# Interface.net
KiCad netlist of a schematic drawn in Altium Designer
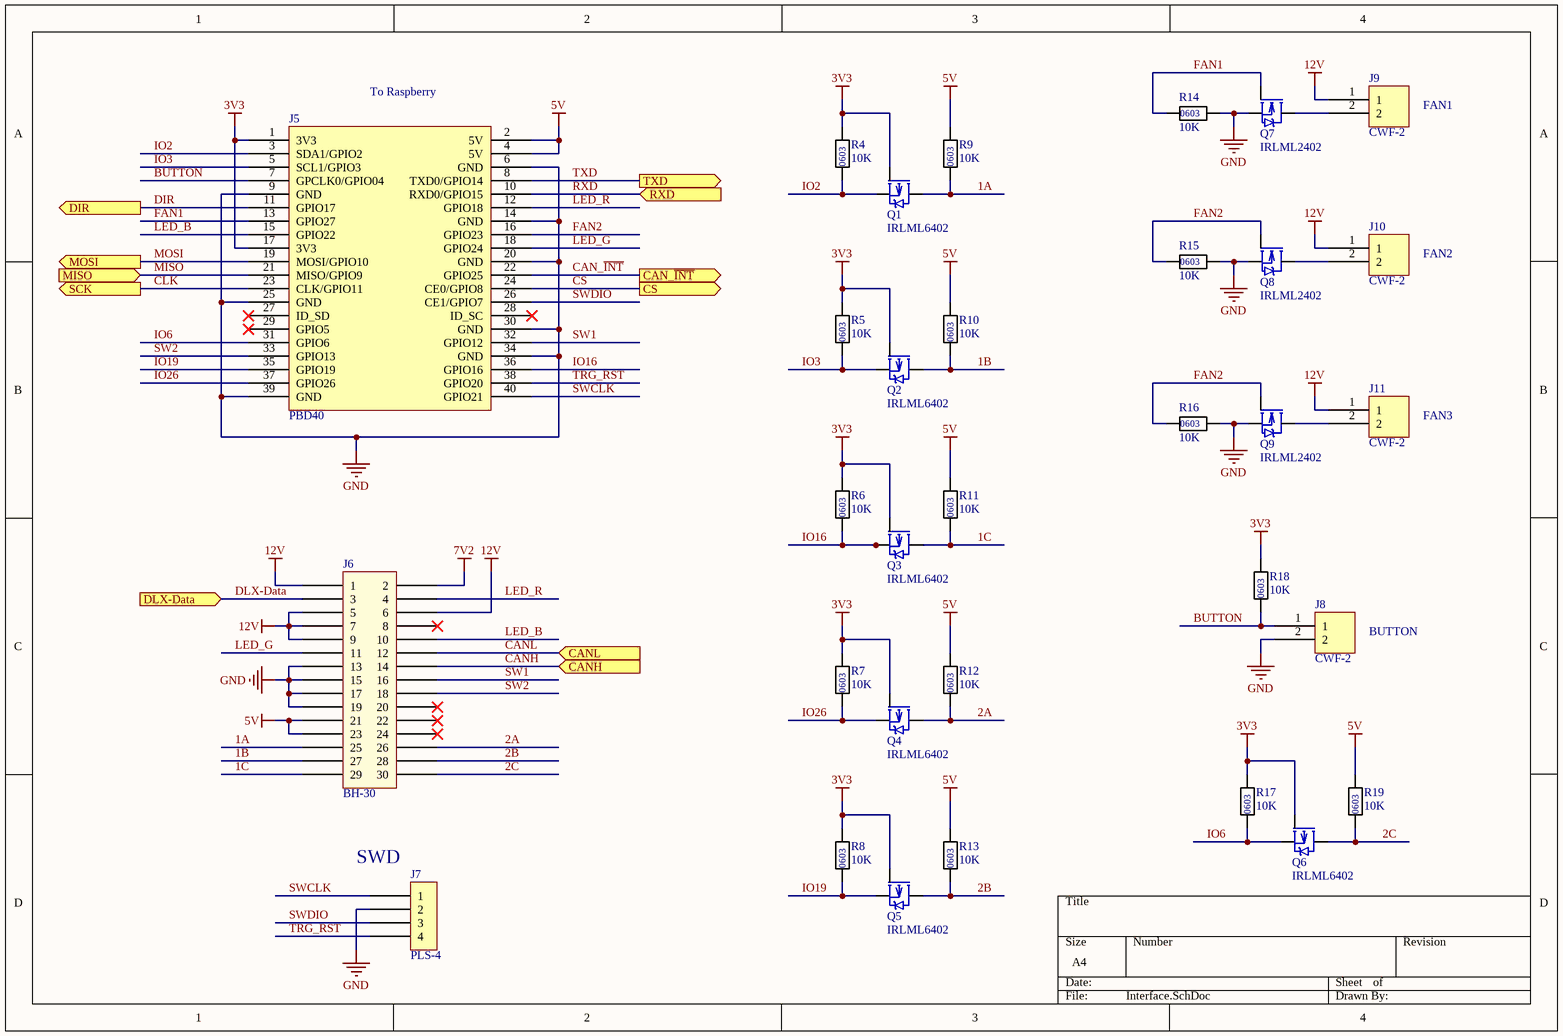
[diagram p0: Interface.SchDoc]

(export (version "E")
  (design (tool "Eeschema 10.0.6"))
  (components
    (comp (ref "J5") (value "PBD40") (footprint "PLD40") (libsource (lib "Popular") (part "RPiGPIO")))
    (comp (ref "J6") (value "BH-30") (footprint "BH-30") (libsource (lib "Popular") (part "BH-30")))
    (comp (ref "J7") (value "PLS-4") (footprint "PLS-4") (libsource (lib "Popular") (part "PLS-4")))
    (comp (ref "J8")
      (value "CWF-2")
      (footprint "CWF-2")
      (description "Connector")
      (libsource (lib "Popular") (part "CWF-2"))
    )
    (comp (ref "J9")
      (value "CWF-2")
      (footprint "CWF-2")
      (description "Connector")
      (libsource (lib "Popular") (part "CWF-2"))
    )
    (comp (ref "J10")
      (value "CWF-2")
      (footprint "CWF-2")
      (description "Connector")
      (libsource (lib "Popular") (part "CWF-2"))
    )
    (comp (ref "J11")
      (value "CWF-2")
      (footprint "CWF-2")
      (description "Connector")
      (libsource (lib "Popular") (part "CWF-2"))
    )
    (comp (ref "Q1")
      (value "IRLML6402")
      (footprint "SOT23")
      (description "p-chanal MOSFET")
      (libsource (lib "Popular") (part "IRLML6402"))
    )
    (comp (ref "Q2")
      (value "IRLML6402")
      (footprint "SOT23")
      (description "p-chanal MOSFET")
      (libsource (lib "Popular") (part "IRLML6402"))
    )
    (comp (ref "Q3")
      (value "IRLML6402")
      (footprint "SOT23")
      (description "p-chanal MOSFET")
      (libsource (lib "Popular") (part "IRLML6402"))
    )
    (comp (ref "Q4")
      (value "IRLML6402")
      (footprint "SOT23")
      (description "p-chanal MOSFET")
      (libsource (lib "Popular") (part "IRLML6402"))
    )
    (comp (ref "Q5")
      (value "IRLML6402")
      (footprint "SOT23")
      (description "p-chanal MOSFET")
      (libsource (lib "Popular") (part "IRLML6402"))
    )
    (comp (ref "Q6")
      (value "IRLML6402")
      (footprint "SOT23")
      (description "p-chanal MOSFET")
      (libsource (lib "Popular") (part "IRLML6402"))
    )
    (comp (ref "Q7")
      (value "IRLML2402")
      (footprint "SOT23")
      (description "n-chanal MOSFET")
      (libsource (lib "Popular") (part "IRLML2402"))
    )
    (comp (ref "Q8")
      (value "IRLML2402")
      (footprint "SOT23")
      (description "n-chanal MOSFET")
      (libsource (lib "Popular") (part "IRLML2402"))
    )
    (comp (ref "Q9")
      (value "IRLML2402")
      (footprint "SOT23")
      (description "n-chanal MOSFET")
      (libsource (lib "Popular") (part "IRLML2402"))
    )
    (comp (ref "R4") (value "10K") (footprint "CHIP_R_0603") (libsource (lib "Popular") (part "RES_0603")))
    (comp (ref "R5") (value "10K") (footprint "CHIP_R_0603") (libsource (lib "Popular") (part "RES_0603")))
    (comp (ref "R6") (value "10K") (footprint "CHIP_R_0603") (libsource (lib "Popular") (part "RES_0603")))
    (comp (ref "R7") (value "10K") (footprint "CHIP_R_0603") (libsource (lib "Popular") (part "RES_0603")))
    (comp (ref "R8") (value "10K") (footprint "CHIP_R_0603") (libsource (lib "Popular") (part "RES_0603")))
    (comp (ref "R9") (value "10K") (footprint "CHIP_R_0603") (libsource (lib "Popular") (part "RES_0603")))
    (comp (ref "R10") (value "10K") (footprint "CHIP_R_0603") (libsource (lib "Popular") (part "RES_0603")))
    (comp (ref "R11") (value "10K") (footprint "CHIP_R_0603") (libsource (lib "Popular") (part "RES_0603")))
    (comp (ref "R12") (value "10K") (footprint "CHIP_R_0603") (libsource (lib "Popular") (part "RES_0603")))
    (comp (ref "R13") (value "10K") (footprint "CHIP_R_0603") (libsource (lib "Popular") (part "RES_0603")))
    (comp (ref "R14") (value "10K") (footprint "CHIP_R_0603") (libsource (lib "Popular") (part "RES_0603")))
    (comp (ref "R15") (value "10K") (footprint "CHIP_R_0603") (libsource (lib "Popular") (part "RES_0603")))
    (comp (ref "R16") (value "10K") (footprint "CHIP_R_0603") (libsource (lib "Popular") (part "RES_0603")))
    (comp (ref "R17") (value "10K") (footprint "CHIP_R_0603") (libsource (lib "Popular") (part "RES_0603")))
    (comp (ref "R18") (value "10K") (footprint "CHIP_R_0603") (libsource (lib "Popular") (part "RES_0603")))
    (comp (ref "R19") (value "10K") (footprint "CHIP_R_0603") (libsource (lib "Popular") (part "RES_0603")))
  )
  (nets
    (net (code "1") (name "/1A") (class "Default")
      (node (ref "J6") (pin "25") (pinfunction "25_25") (pintype "passive"))
      (node (ref "Q1") (pin "3") (pinfunction "D_3") (pintype "passive"))
      (node (ref "R9") (pin "1") (pinfunction "1_1") (pintype "passive"))
    )
    (net (code "2") (name "/1B") (class "Default")
      (node (ref "J6") (pin "27") (pinfunction "27_27") (pintype "passive"))
      (node (ref "Q2") (pin "3") (pinfunction "D_3") (pintype "passive"))
      (node (ref "R10") (pin "1") (pinfunction "1_1") (pintype "passive"))
    )
    (net (code "3") (name "/1C") (class "Default")
      (node (ref "J6") (pin "29") (pinfunction "29_29") (pintype "passive"))
      (node (ref "Q3") (pin "3") (pinfunction "D_3") (pintype "passive"))
      (node (ref "R11") (pin "1") (pinfunction "1_1") (pintype "passive"))
    )
    (net (code "4") (name "/2A") (class "Default")
      (node (ref "J6") (pin "26") (pinfunction "26_26") (pintype "passive"))
      (node (ref "Q4") (pin "3") (pinfunction "D_3") (pintype "passive"))
      (node (ref "R12") (pin "1") (pinfunction "1_1") (pintype "passive"))
    )
    (net (code "5") (name "/2B") (class "Default")
      (node (ref "J6") (pin "28") (pinfunction "28_28") (pintype "passive"))
      (node (ref "Q5") (pin "3") (pinfunction "D_3") (pintype "passive"))
      (node (ref "R13") (pin "1") (pinfunction "1_1") (pintype "passive"))
    )
    (net (code "6") (name "/2C") (class "Default")
      (node (ref "J6") (pin "30") (pinfunction "30_30") (pintype "passive"))
      (node (ref "Q6") (pin "3") (pinfunction "D_3") (pintype "passive"))
      (node (ref "R19") (pin "1") (pinfunction "1_1") (pintype "passive"))
    )
    (net (code "7") (name "/BUTTON") (class "Default")
      (node (ref "J5") (pin "7") (pinfunction "GPCLK0/GPIO04_7") (pintype "passive"))
      (node (ref "J8") (pin "1") (pinfunction "1_1") (pintype "passive"))
      (node (ref "R18") (pin "1") (pinfunction "1_1") (pintype "passive"))
    )
    (net (code "8") (name "/CANH") (class "Default")
      (node (ref "J6") (pin "14") (pinfunction "14_14") (pintype "passive"))
    )
    (net (code "9") (name "/CANL") (class "Default")
      (node (ref "J6") (pin "12") (pinfunction "12_12") (pintype "passive"))
    )
    (net (code "10") (name "/CAN_~{INT}") (class "Default")
      (node (ref "J5") (pin "22") (pinfunction "GPIO25_22") (pintype "passive"))
    )
    (net (code "11") (name "/CLK") (class "Default")
      (node (ref "J5") (pin "23") (pinfunction "CLK/GPIO11_23") (pintype "passive"))
    )
    (net (code "12") (name "/CS") (class "Default")
      (node (ref "J5") (pin "24") (pinfunction "CE0/GPIO8_24") (pintype "passive"))
    )
    (net (code "13") (name "/DIR") (class "Default")
      (node (ref "J5") (pin "11") (pinfunction "GPIO17_11") (pintype "passive"))
    )
    (net (code "14") (name "/DLX-Data") (class "Default")
      (node (ref "J6") (pin "3") (pinfunction "3_3") (pintype "passive"))
    )
    (net (code "15") (name "/FAN1") (class "Default")
      (node (ref "J5") (pin "13") (pinfunction "GPIO27_13") (pintype "passive"))
      (node (ref "Q7") (pin "1") (pinfunction "G_1") (pintype "passive"))
      (node (ref "R14") (pin "1") (pinfunction "1_1") (pintype "passive"))
    )
    (net (code "16") (name "/FAN2") (class "Default")
      (node (ref "J5") (pin "16") (pinfunction "GPIO23_16") (pintype "passive"))
      (node (ref "Q8") (pin "1") (pinfunction "G_1") (pintype "passive"))
      (node (ref "Q9") (pin "1") (pinfunction "G_1") (pintype "passive"))
      (node (ref "R15") (pin "1") (pinfunction "1_1") (pintype "passive"))
      (node (ref "R16") (pin "1") (pinfunction "1_1") (pintype "passive"))
    )
    (net (code "17") (name "/IO2") (class "Default")
      (node (ref "J5") (pin "3") (pinfunction "SDA1/GPIO2_3") (pintype "passive"))
      (node (ref "Q1") (pin "2") (pinfunction "S_2") (pintype "passive"))
      (node (ref "R4") (pin "1") (pinfunction "1_1") (pintype "passive"))
    )
    (net (code "18") (name "/IO3") (class "Default")
      (node (ref "J5") (pin "5") (pinfunction "SCL1/GPIO3_5") (pintype "passive"))
      (node (ref "Q2") (pin "2") (pinfunction "S_2") (pintype "passive"))
      (node (ref "R5") (pin "1") (pinfunction "1_1") (pintype "passive"))
    )
    (net (code "19") (name "/IO6") (class "Default")
      (node (ref "J5") (pin "31") (pinfunction "GPIO6_31") (pintype "passive"))
      (node (ref "Q6") (pin "2") (pinfunction "S_2") (pintype "passive"))
      (node (ref "R17") (pin "1") (pinfunction "1_1") (pintype "passive"))
    )
    (net (code "20") (name "/IO16") (class "Default")
      (node (ref "J5") (pin "36") (pinfunction "GPIO16_36") (pintype "passive"))
      (node (ref "Q3") (pin "2") (pinfunction "S_2") (pintype "passive"))
      (node (ref "R6") (pin "1") (pinfunction "1_1") (pintype "passive"))
    )
    (net (code "21") (name "/IO19") (class "Default")
      (node (ref "J5") (pin "35") (pinfunction "GPIO19_35") (pintype "passive"))
      (node (ref "Q5") (pin "2") (pinfunction "S_2") (pintype "passive"))
      (node (ref "R8") (pin "1") (pinfunction "1_1") (pintype "passive"))
    )
    (net (code "22") (name "/IO26") (class "Default")
      (node (ref "J5") (pin "37") (pinfunction "GPIO26_37") (pintype "passive"))
      (node (ref "Q4") (pin "2") (pinfunction "S_2") (pintype "passive"))
      (node (ref "R7") (pin "1") (pinfunction "1_1") (pintype "passive"))
    )
    (net (code "23") (name "/LED_B") (class "Default")
      (node (ref "J5") (pin "15") (pinfunction "GPIO22_15") (pintype "passive"))
      (node (ref "J6") (pin "10") (pinfunction "10_10") (pintype "passive"))
    )
    (net (code "24") (name "/LED_G") (class "Default")
      (node (ref "J5") (pin "18") (pinfunction "GPIO24_18") (pintype "passive"))
      (node (ref "J6") (pin "11") (pinfunction "11_11") (pintype "passive"))
    )
    (net (code "25") (name "/LED_R") (class "Default")
      (node (ref "J5") (pin "12") (pinfunction "GPIO18_12") (pintype "passive"))
      (node (ref "J6") (pin "4") (pinfunction "4_4") (pintype "passive"))
    )
    (net (code "26") (name "/MISO") (class "Default")
      (node (ref "J5") (pin "21") (pinfunction "MISO/GPIO9_21") (pintype "passive"))
    )
    (net (code "27") (name "/MOSI") (class "Default")
      (node (ref "J5") (pin "19") (pinfunction "MOSI/GPIO10_19") (pintype "passive"))
    )
    (net (code "28") (name "/RXD") (class "Default")
      (node (ref "J5") (pin "10") (pinfunction "RXD0/GPIO15_10") (pintype "passive"))
    )
    (net (code "29") (name "/SW1") (class "Default")
      (node (ref "J5") (pin "32") (pinfunction "GPIO12_32") (pintype "passive"))
      (node (ref "J6") (pin "16") (pinfunction "16_16") (pintype "passive"))
    )
    (net (code "30") (name "/SW2") (class "Default")
      (node (ref "J5") (pin "33") (pinfunction "GPIO13_33") (pintype "passive"))
      (node (ref "J6") (pin "18") (pinfunction "18_18") (pintype "passive"))
    )
    (net (code "31") (name "/SWCLK") (class "Default")
      (node (ref "J5") (pin "40") (pinfunction "GPIO21_40") (pintype "passive"))
      (node (ref "J7") (pin "1") (pinfunction "1_1") (pintype "passive"))
    )
    (net (code "32") (name "/SWDIO") (class "Default")
      (node (ref "J5") (pin "26") (pinfunction "CE1/GPIO7_26") (pintype "passive"))
      (node (ref "J7") (pin "3") (pinfunction "3_3") (pintype "passive"))
    )
    (net (code "33") (name "/TRG_RST") (class "Default")
      (node (ref "J5") (pin "38") (pinfunction "GPIO20_38") (pintype "passive"))
      (node (ref "J7") (pin "4") (pinfunction "4_4") (pintype "passive"))
    )
    (net (code "34") (name "/TXD") (class "Default")
      (node (ref "J5") (pin "8") (pinfunction "TXD0/GPIO14_8") (pintype "passive"))
    )
    (net (code "35") (name "3V3") (class "Default")
      (node (ref "J5") (pin "1") (pinfunction "3V3_1") (pintype "passive"))
      (node (ref "J5") (pin "17") (pinfunction "3V3_17") (pintype "passive"))
      (node (ref "Q1") (pin "1") (pinfunction "G_1") (pintype "passive"))
      (node (ref "Q2") (pin "1") (pinfunction "G_1") (pintype "passive"))
      (node (ref "Q3") (pin "1") (pinfunction "G_1") (pintype "passive"))
      (node (ref "Q4") (pin "1") (pinfunction "G_1") (pintype "passive"))
      (node (ref "Q5") (pin "1") (pinfunction "G_1") (pintype "passive"))
      (node (ref "Q6") (pin "1") (pinfunction "G_1") (pintype "passive"))
      (node (ref "R17") (pin "2") (pinfunction "2_2") (pintype "passive"))
      (node (ref "R18") (pin "2") (pinfunction "2_2") (pintype "passive"))
      (node (ref "R4") (pin "2") (pinfunction "2_2") (pintype "passive"))
      (node (ref "R5") (pin "2") (pinfunction "2_2") (pintype "passive"))
      (node (ref "R6") (pin "2") (pinfunction "2_2") (pintype "passive"))
      (node (ref "R7") (pin "2") (pinfunction "2_2") (pintype "passive"))
      (node (ref "R8") (pin "2") (pinfunction "2_2") (pintype "passive"))
    )
    (net (code "36") (name "5V") (class "Default")
      (node (ref "J5") (pin "2") (pinfunction "5V_2") (pintype "passive"))
      (node (ref "J5") (pin "4") (pinfunction "5V_4") (pintype "passive"))
      (node (ref "J6") (pin "21") (pinfunction "21_21") (pintype "passive"))
      (node (ref "J6") (pin "23") (pinfunction "23_23") (pintype "passive"))
      (node (ref "R10") (pin "2") (pinfunction "2_2") (pintype "passive"))
      (node (ref "R11") (pin "2") (pinfunction "2_2") (pintype "passive"))
      (node (ref "R12") (pin "2") (pinfunction "2_2") (pintype "passive"))
      (node (ref "R13") (pin "2") (pinfunction "2_2") (pintype "passive"))
      (node (ref "R19") (pin "2") (pinfunction "2_2") (pintype "passive"))
      (node (ref "R9") (pin "2") (pinfunction "2_2") (pintype "passive"))
    )
    (net (code "37") (name "7V2") (class "Default")
      (node (ref "J6") (pin "2") (pinfunction "2_2") (pintype "passive"))
    )
    (net (code "38") (name "12V") (class "Default")
      (node (ref "J10") (pin "1") (pinfunction "1_1") (pintype "passive"))
      (node (ref "J11") (pin "1") (pinfunction "1_1") (pintype "passive"))
      (node (ref "J6") (pin "1") (pinfunction "1_1") (pintype "passive"))
      (node (ref "J6") (pin "5") (pinfunction "5_5") (pintype "passive"))
      (node (ref "J6") (pin "6") (pinfunction "6_6") (pintype "passive"))
      (node (ref "J6") (pin "7") (pinfunction "7_7") (pintype "passive"))
      (node (ref "J6") (pin "9") (pinfunction "9_9") (pintype "passive"))
      (node (ref "J9") (pin "1") (pinfunction "1_1") (pintype "passive"))
    )
    (net (code "39") (name "GND") (class "Default")
      (node (ref "J5") (pin "14") (pinfunction "GND_14") (pintype "passive"))
      (node (ref "J5") (pin "20") (pinfunction "GND_20") (pintype "passive"))
      (node (ref "J5") (pin "25") (pinfunction "GND_25") (pintype "passive"))
      (node (ref "J5") (pin "30") (pinfunction "GND_30") (pintype "passive"))
      (node (ref "J5") (pin "34") (pinfunction "GND_34") (pintype "passive"))
      (node (ref "J5") (pin "39") (pinfunction "GND_39") (pintype "passive"))
      (node (ref "J5") (pin "6") (pinfunction "GND_6") (pintype "passive"))
      (node (ref "J5") (pin "9") (pinfunction "GND_9") (pintype "passive"))
      (node (ref "J6") (pin "13") (pinfunction "13_13") (pintype "passive"))
      (node (ref "J6") (pin "15") (pinfunction "15_15") (pintype "passive"))
      (node (ref "J6") (pin "17") (pinfunction "17_17") (pintype "passive"))
      (node (ref "J6") (pin "19") (pinfunction "19_19") (pintype "passive"))
      (node (ref "J7") (pin "2") (pinfunction "2_2") (pintype "passive"))
      (node (ref "J8") (pin "2") (pinfunction "2_2") (pintype "passive"))
      (node (ref "Q7") (pin "2") (pinfunction "S_2") (pintype "passive"))
      (node (ref "Q8") (pin "2") (pinfunction "S_2") (pintype "passive"))
      (node (ref "Q9") (pin "2") (pinfunction "S_2") (pintype "passive"))
      (node (ref "R14") (pin "2") (pinfunction "2_2") (pintype "passive"))
      (node (ref "R15") (pin "2") (pinfunction "2_2") (pintype "passive"))
      (node (ref "R16") (pin "2") (pinfunction "2_2") (pintype "passive"))
    )
    (net (code "40") (name "Net-(Q7-D)") (class "Default")
      (node (ref "J9") (pin "2") (pinfunction "2_2") (pintype "passive"))
      (node (ref "Q7") (pin "3") (pinfunction "D_3") (pintype "passive"))
    )
    (net (code "41") (name "Net-(Q8-D)") (class "Default")
      (node (ref "J10") (pin "2") (pinfunction "2_2") (pintype "passive"))
      (node (ref "Q8") (pin "3") (pinfunction "D_3") (pintype "passive"))
    )
    (net (code "42") (name "Net-(Q9-D)") (class "Default")
      (node (ref "J11") (pin "2") (pinfunction "2_2") (pintype "passive"))
      (node (ref "Q9") (pin "3") (pinfunction "D_3") (pintype "passive"))
    )
    (net (code "43") (name "unconnected-(J5-GPIO5-Pad29)") (class "Default")
      (node (ref "J5") (pin "29") (pinfunction "GPIO5_29") (pintype "passive+no_connect"))
    )
    (net (code "44") (name "unconnected-(J5-ID_SC-Pad28)") (class "Default")
      (node (ref "J5") (pin "28") (pinfunction "ID_SC_28") (pintype "passive+no_connect"))
    )
    (net (code "45") (name "unconnected-(J5-ID_SD-Pad27)") (class "Default")
      (node (ref "J5") (pin "27") (pinfunction "ID_SD_27") (pintype "passive+no_connect"))
    )
    (net (code "46") (name "unconnected-(J6-Pad8)") (class "Default")
      (node (ref "J6") (pin "8") (pinfunction "8_8") (pintype "passive+no_connect"))
    )
    (net (code "47") (name "unconnected-(J6-Pad20)") (class "Default")
      (node (ref "J6") (pin "20") (pinfunction "20_20") (pintype "passive+no_connect"))
    )
    (net (code "48") (name "unconnected-(J6-Pad22)") (class "Default")
      (node (ref "J6") (pin "22") (pinfunction "22_22") (pintype "passive+no_connect"))
    )
    (net (code "49") (name "unconnected-(J6-Pad24)") (class "Default")
      (node (ref "J6") (pin "24") (pinfunction "24_24") (pintype "passive+no_connect"))
    )
  )
)
